# External.net
KiCad netlist of a schematic drawn in Altium Designer
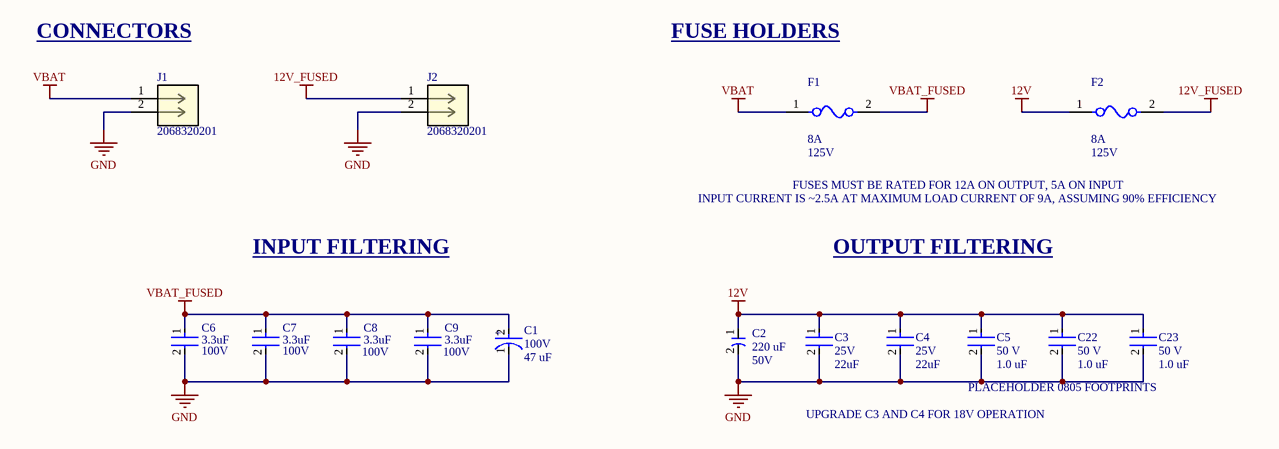
[diagram p0: External.SchDoc]

(export (version "E")
  (design (tool "Eeschema 10.0.6"))
  (components
    (comp (ref "C1")
      (value "UUX2A470MNL1GS")
      (footprint "PCAP_10x10-ELECT_NCA")
      (description "47 µF 100 V Aluminum Electrolytic Capacitors Radial, Can - SMD 2000 Hrs @ 105°C")
      (fields (field (name "VOLTAGE") "100V") (field (name "CAPACITANCE") "47 uF"))
      (libsource (lib "JLC_25") (part "CAP-47U-0005"))
    )
    (comp (ref "C2")
      (value "50TZV220M10X10.5")
      (footprint "ELEC-220U-0003")
      (description "220 µF 50 V Aluminum Electrolytic Capacitors Radial, Can - SMD 2000 Hrs @ 105°C")
      (fields (field (name "CAPACITANCE") "220 uF") (field (name "VOLTAGE RATING") "50V"))
      (libsource (lib "MasterLib") (part "ELEC-220U-0003"))
    )
    (comp (ref "C3")
      (value "GRM32ER61E226KE15L")
      (footprint "CAP-1210")
      (description "CAP CER 22UF 25V X5R 1210")
      (fields (field (name "VOLTAGE") "25V") (field (name "CAPACITANCE") "22uF"))
      (libsource (lib "JLC_25") (part "CAP-22U-0001"))
    )
    (comp (ref "C4")
      (value "GRM32ER61E226KE15L")
      (footprint "CAP-1210")
      (description "CAP CER 22UF 25V X5R 1210")
      (fields (field (name "VOLTAGE") "25V") (field (name "CAPACITANCE") "22uF"))
      (libsource (lib "JLC_25") (part "CAP-22U-0001"))
    )
    (comp (ref "C5")
      (value "CC0805KKX7R9BB105")
      (footprint "CAP-0805")
      (description "CAP CER 1UF 50V X7R 0805")
      (fields (field (name "VOLTAGE") "50 V") (field (name "CAPACITANCE") "1.0 uF"))
      (libsource (lib "JLC_25") (part "CAP-1U-0001"))
    )
    (comp (ref "C6")
      (value "C3216X7S2A335K160AB")
      (footprint "CAP-1206")
      (description "CAP CER 3.3UF 100V X7S 1206")
      (fields (field (name "CAPACITANCE") "3.3uF") (field (name "VOLTAGE") "100V"))
      (libsource (lib "JLC_25") (part "CAP-3.3U-0001"))
    )
    (comp (ref "C7")
      (value "C3216X7S2A335K160AB")
      (footprint "CAP-1206")
      (description "CAP CER 3.3UF 100V X7S 1206")
      (fields (field (name "CAPACITANCE") "3.3uF") (field (name "VOLTAGE") "100V"))
      (libsource (lib "JLC_25") (part "CAP-3.3U-0001"))
    )
    (comp (ref "C8")
      (value "C3216X7S2A335K160AB")
      (footprint "CAP-1206")
      (description "CAP CER 3.3UF 100V X7S 1206")
      (fields (field (name "CAPACITANCE") "3.3uF") (field (name "VOLTAGE") "100V"))
      (libsource (lib "JLC_25") (part "CAP-3.3U-0001"))
    )
    (comp (ref "C9")
      (value "C3216X7S2A335K160AB")
      (footprint "CAP-1206")
      (description "CAP CER 3.3UF 100V X7S 1206")
      (fields (field (name "CAPACITANCE") "3.3uF") (field (name "VOLTAGE") "100V"))
      (libsource (lib "JLC_25") (part "CAP-3.3U-0001"))
    )
    (comp (ref "C22")
      (value "CC0805KKX7R9BB105")
      (footprint "CAP-0805")
      (description "CAP CER 1UF 50V X7R 0805")
      (fields (field (name "VOLTAGE") "50 V") (field (name "CAPACITANCE") "1.0 uF"))
      (libsource (lib "JLC_25") (part "CAP-1U-0001"))
    )
    (comp (ref "C23")
      (value "CC0805KKX7R9BB105")
      (footprint "CAP-0805")
      (description "CAP CER 1UF 50V X7R 0805")
      (fields (field (name "VOLTAGE") "50 V") (field (name "CAPACITANCE") "1.0 uF"))
      (libsource (lib "JLC_25") (part "CAP-1U-0001"))
    )
    (comp (ref "F1")
      (value "01550900M")
      (footprint "FUSE-0001")
      (description "FUSE BLOK CARTRIDGE 125V 10A SMD")
      (fields (field (name "FUSE CURRENT") "8A") (field (name "VOLTAGE RATING") "125V"))
      (libsource (lib "JLC_25") (part "FUSE-0001"))
    )
    (comp (ref "F2")
      (value "01550900M")
      (footprint "FUSE-0001")
      (description "FUSE BLOK CARTRIDGE 125V 10A SMD")
      (fields (field (name "FUSE CURRENT") "8A") (field (name "VOLTAGE RATING") "125V"))
      (libsource (lib "JLC_25") (part "FUSE-0001"))
    )
    (comp (ref "J1")
      (value "2068320201")
      (footprint "CONN_2068320000-SD_02_MOL")
      (fields (field (name "COPYRIGHT") "Copyright (C) 2025 Ultra Librarian. All rights reserved."))
      (libsource (lib "MasterLib") (part "2068320201"))
    )
    (comp (ref "J2")
      (value "2068320201")
      (footprint "CONN_2068320000-SD_02_MOL")
      (fields (field (name "COPYRIGHT") "Copyright (C) 2025 Ultra Librarian. All rights reserved."))
      (libsource (lib "MasterLib") (part "2068320201"))
    )
  )
  (nets
    (net (code "1") (name "12V") (class "Default")
      (node (ref "C2") (pin "1") (pinfunction "1_1") (pintype "passive"))
      (node (ref "C22") (pin "1") (pinfunction "1_1") (pintype "passive"))
      (node (ref "C23") (pin "1") (pinfunction "1_1") (pintype "passive"))
      (node (ref "C3") (pin "1") (pinfunction "1_1") (pintype "passive"))
      (node (ref "C4") (pin "1") (pinfunction "1_1") (pintype "passive"))
      (node (ref "C5") (pin "1") (pinfunction "1_1") (pintype "passive"))
      (node (ref "F2") (pin "1") (pinfunction "1_1") (pintype "passive"))
    )
    (net (code "2") (name "12V_FUSED") (class "Default")
      (node (ref "F2") (pin "2") (pinfunction "2_2") (pintype "passive"))
      (node (ref "J2") (pin "1") (pinfunction "1_1") (pintype "passive"))
    )
    (net (code "3") (name "GND") (class "Default")
      (node (ref "C1") (pin "1") (pinfunction "C_1") (pintype "passive"))
      (node (ref "C2") (pin "2") (pinfunction "2_2") (pintype "passive"))
      (node (ref "C22") (pin "2") (pinfunction "2_2") (pintype "passive"))
      (node (ref "C23") (pin "2") (pinfunction "2_2") (pintype "passive"))
      (node (ref "C3") (pin "2") (pinfunction "2_2") (pintype "passive"))
      (node (ref "C4") (pin "2") (pinfunction "2_2") (pintype "passive"))
      (node (ref "C5") (pin "2") (pinfunction "2_2") (pintype "passive"))
      (node (ref "C6") (pin "2") (pinfunction "2_2") (pintype "passive"))
      (node (ref "C7") (pin "2") (pinfunction "2_2") (pintype "passive"))
      (node (ref "C8") (pin "2") (pinfunction "2_2") (pintype "passive"))
      (node (ref "C9") (pin "2") (pinfunction "2_2") (pintype "passive"))
      (node (ref "J1") (pin "2") (pinfunction "2_2") (pintype "passive"))
      (node (ref "J2") (pin "2") (pinfunction "2_2") (pintype "passive"))
    )
    (net (code "4") (name "VBAT") (class "Default")
      (node (ref "F1") (pin "1") (pinfunction "1_1") (pintype "passive"))
      (node (ref "J1") (pin "1") (pinfunction "1_1") (pintype "passive"))
    )
    (net (code "5") (name "VBAT_FUSED") (class "Default")
      (node (ref "C1") (pin "2") (pinfunction "A_2") (pintype "passive"))
      (node (ref "C6") (pin "1") (pinfunction "1_1") (pintype "passive"))
      (node (ref "C7") (pin "1") (pinfunction "1_1") (pintype "passive"))
      (node (ref "C8") (pin "1") (pinfunction "1_1") (pintype "passive"))
      (node (ref "C9") (pin "1") (pinfunction "1_1") (pintype "passive"))
      (node (ref "F1") (pin "2") (pinfunction "2_2") (pintype "passive"))
    )
  )
)
